# OpenCoffee_V2_DBL_Test.net
KiCad netlist of a schematic drawn in EAGLE
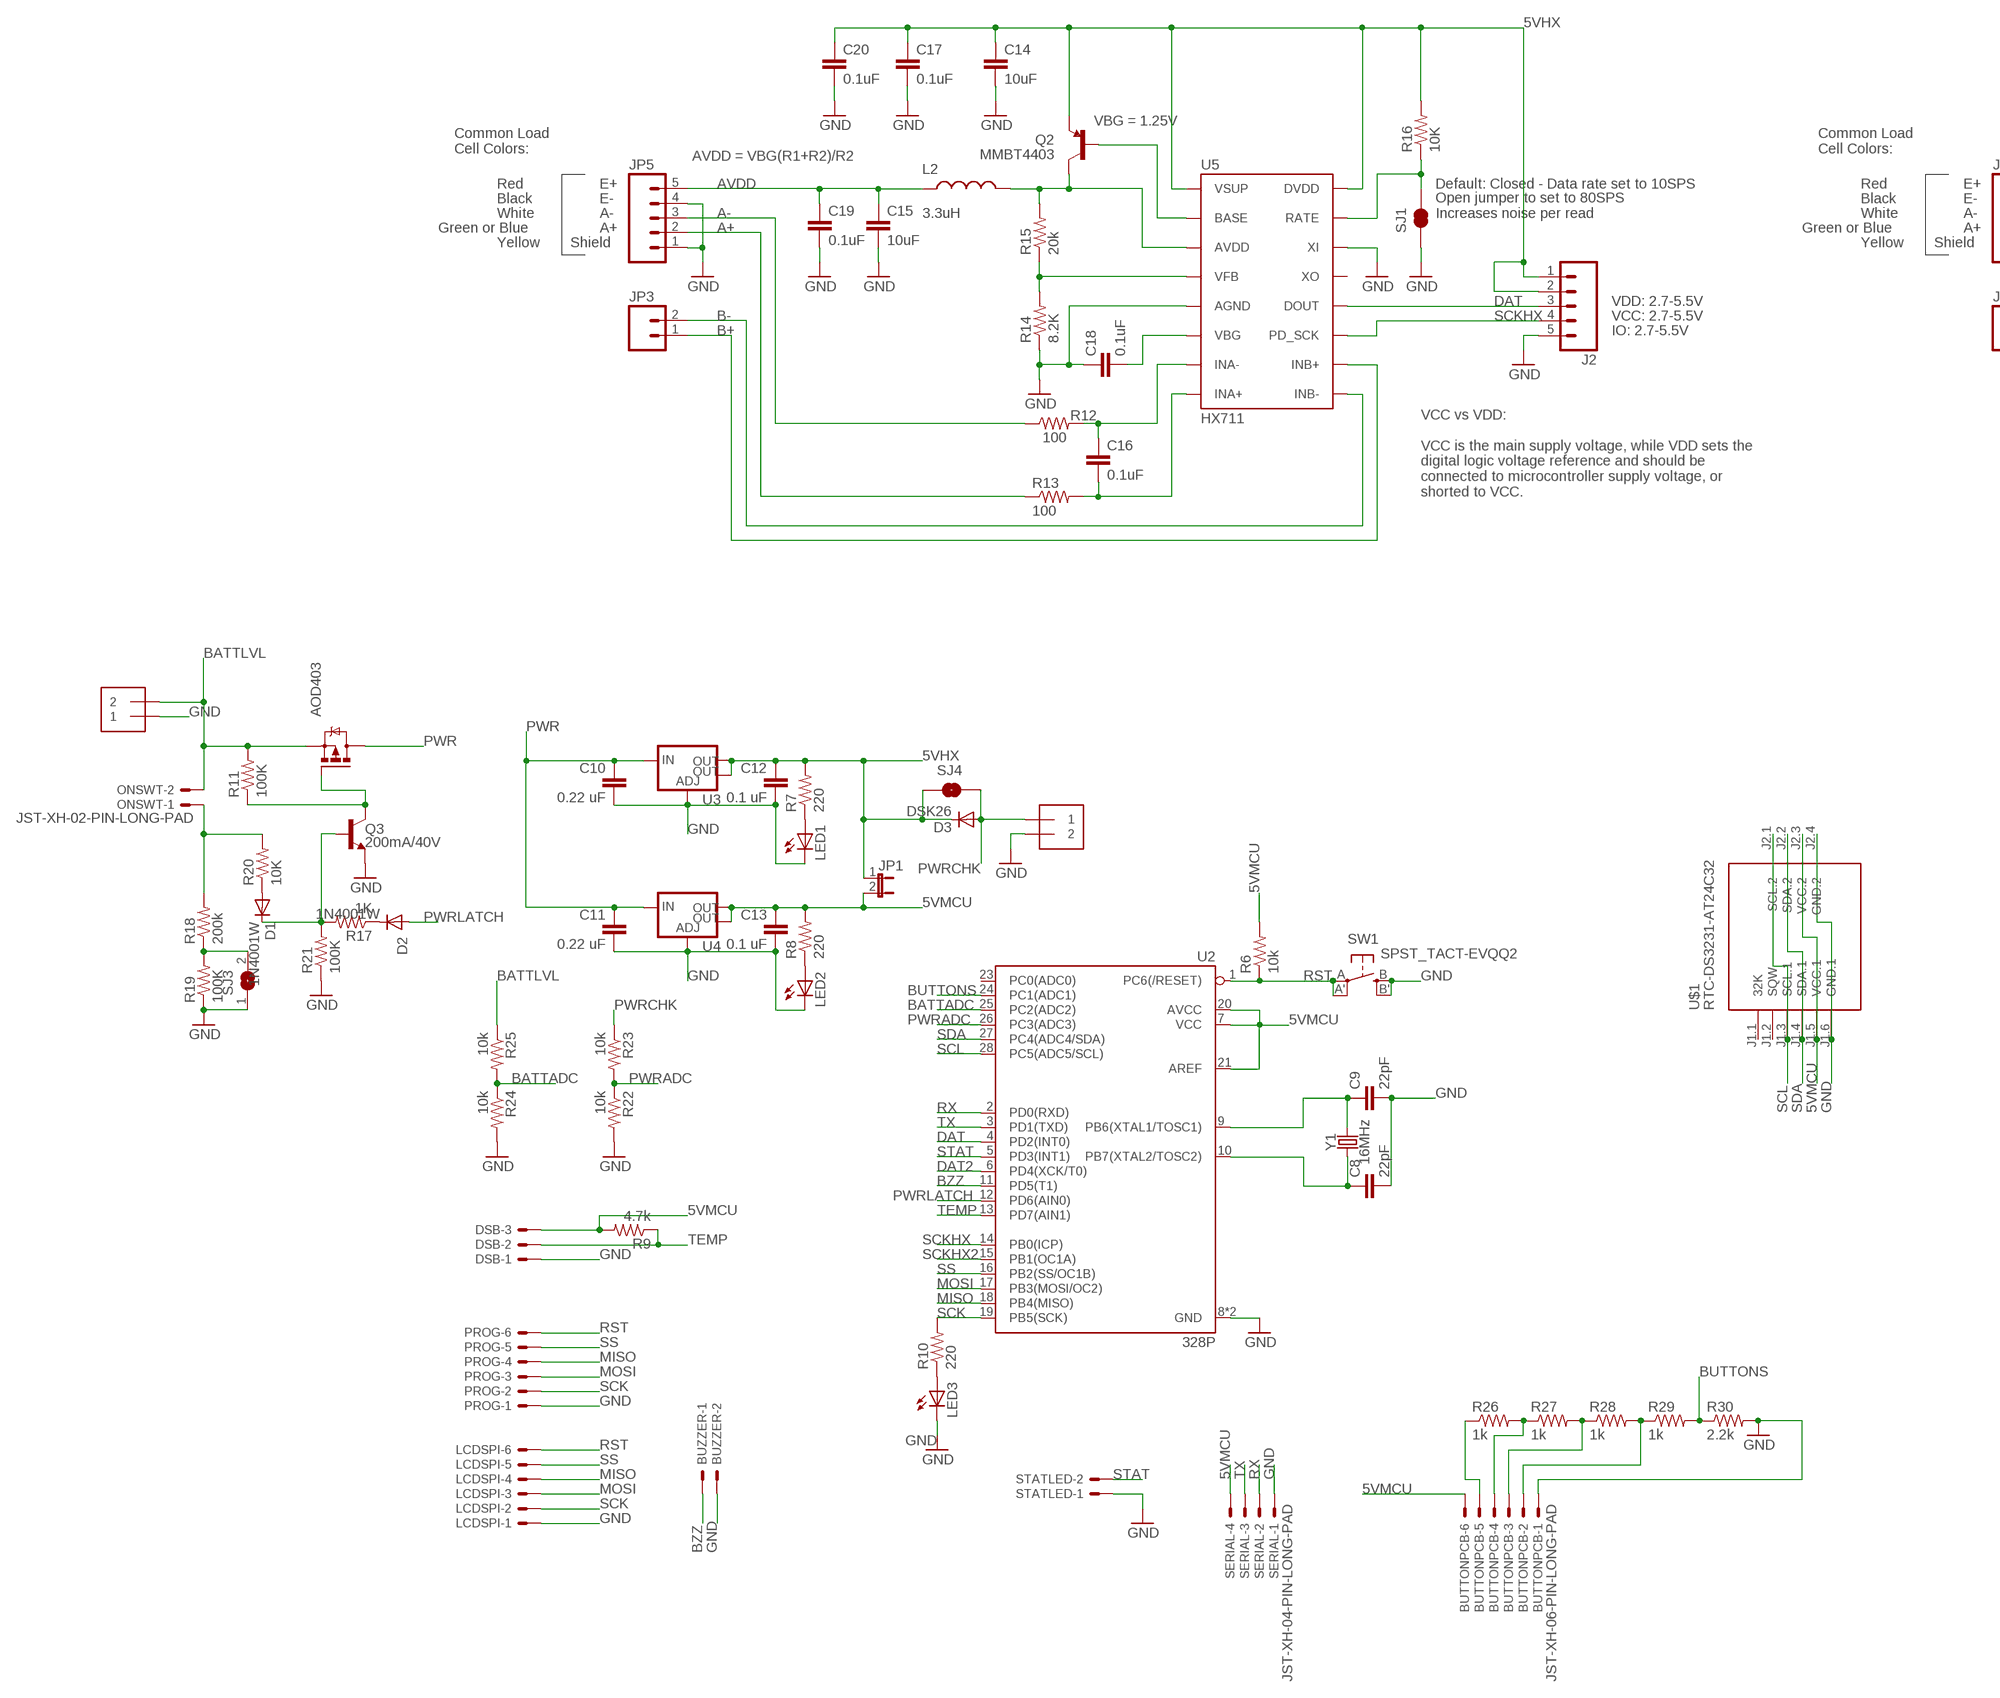
[diagram p0: schematic, sheet 1, part 1 of 2]
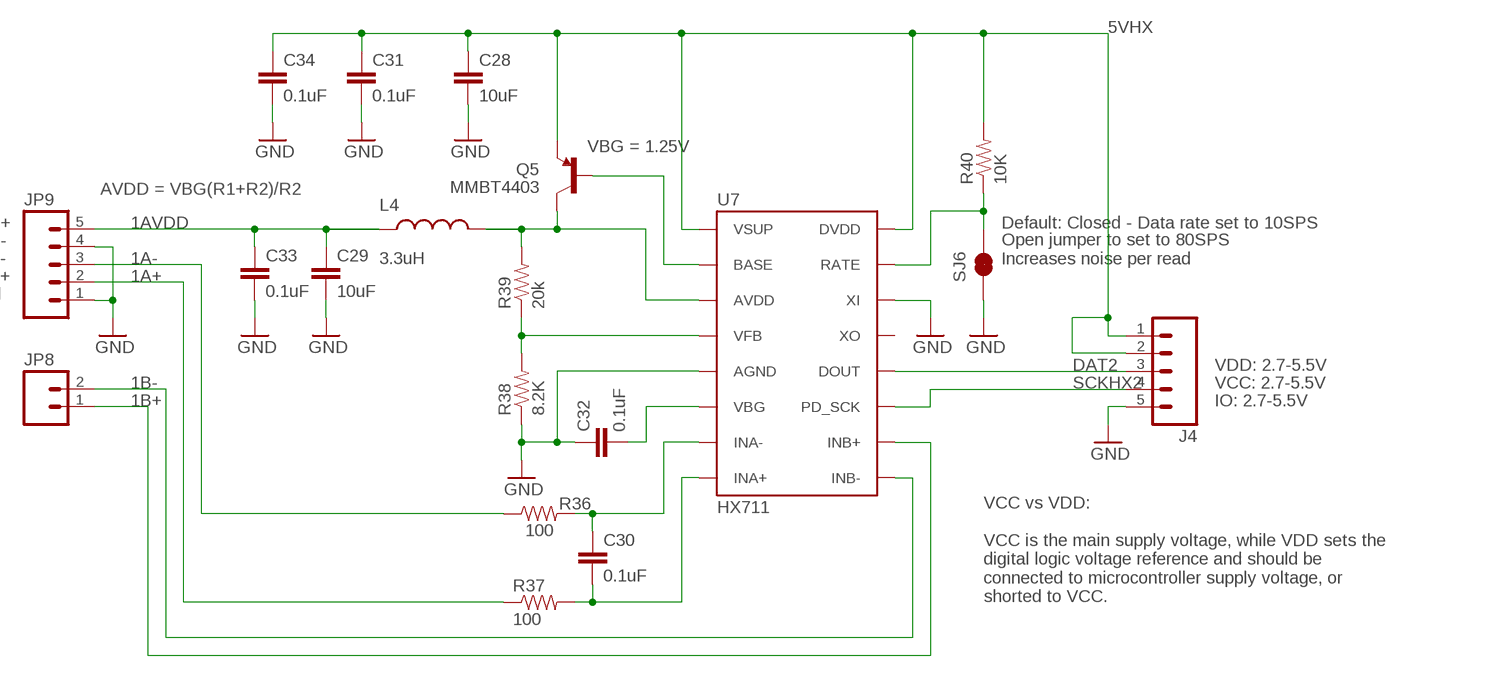
[diagram p1: schematic, sheet 1, part 2 of 2]

(export (version "E")
  (design (tool "Eeschema 10.0.6"))
  (components
    (comp (ref "AOD403")
      (value "IRFR5305")
      (footprint "eagle-import:D-PAK_TO252AA")
      (libsource (lib "eagle-import") (part "IRF?5305R"))
    )
    (comp (ref "BATT")
      (value "1X2-3.5MM")
      (footprint "eagle-import:1X2-3.5MM")
      (libsource (lib "eagle-import") (part "1X2-3.5MM"))
    )
    (comp (ref "BUTTONPCB")
      (value "JST-XH-06-PIN-LONG-PAD")
      (footprint "eagle-import:JST-XH-06-PACKAGE-LONG-PAD")
      (libsource (lib "eagle-import") (part "JST-XH-06-PIN-LONG-PAD"))
    )
    (comp (ref "BUZZER")
      (value "JST-XH-02-PIN-LONG-PAD")
      (footprint "eagle-import:JST-XH-02-PACKAGE-LONG-PAD")
      (libsource (lib "eagle-import") (part "JST-XH-02-PIN-LONG-PAD"))
    )
    (comp (ref "C8")
      (value "22pF")
      (footprint "eagle-import:C1206")
      (libsource (lib "eagle-import") (part "C-EUC1206"))
    )
    (comp (ref "C9")
      (value "22pF")
      (footprint "eagle-import:C1206")
      (libsource (lib "eagle-import") (part "C-EUC1206"))
    )
    (comp (ref "C10")
      (value "0.22 uF")
      (footprint "eagle-import:C1206")
      (libsource (lib "eagle-import") (part "C-EUC1206"))
    )
    (comp (ref "C11")
      (value "0.22 uF")
      (footprint "eagle-import:C1206")
      (libsource (lib "eagle-import") (part "C-EUC1206"))
    )
    (comp (ref "C12")
      (value "0.1 uF")
      (footprint "eagle-import:C1206")
      (libsource (lib "eagle-import") (part "C-EUC1206"))
    )
    (comp (ref "C13")
      (value "0.1 uF")
      (footprint "eagle-import:C1206")
      (libsource (lib "eagle-import") (part "C-EUC1206"))
    )
    (comp (ref "C14")
      (value "10uF")
      (footprint "eagle-import:1210")
      (libsource (lib "eagle-import") (part "10UF50V20%(1210)"))
    )
    (comp (ref "C15")
      (value "10uF")
      (footprint "eagle-import:1210")
      (libsource (lib "eagle-import") (part "10UF50V20%(1210)"))
    )
    (comp (ref "C16")
      (value "0.1uF")
      (footprint "eagle-import:0603-CAP")
      (libsource (lib "eagle-import") (part "0.1UF-25V-5%(0603)"))
    )
    (comp (ref "C17")
      (value "0.1uF")
      (footprint "eagle-import:0603-CAP")
      (libsource (lib "eagle-import") (part "0.1UF-25V-5%(0603)"))
    )
    (comp (ref "C18")
      (value "0.1uF")
      (footprint "eagle-import:0603-CAP")
      (libsource (lib "eagle-import") (part "0.1UF-25V-5%(0603)"))
    )
    (comp (ref "C19")
      (value "0.1uF")
      (footprint "eagle-import:0603-CAP")
      (libsource (lib "eagle-import") (part "0.1UF-25V-5%(0603)"))
    )
    (comp (ref "C20")
      (value "0.1uF")
      (footprint "eagle-import:0603-CAP")
      (libsource (lib "eagle-import") (part "0.1UF-25V-5%(0603)"))
    )
    (comp (ref "C28")
      (value "10uF")
      (footprint "eagle-import:1210")
      (libsource (lib "eagle-import") (part "10UF50V20%(1210)"))
    )
    (comp (ref "C29")
      (value "10uF")
      (footprint "eagle-import:1210")
      (libsource (lib "eagle-import") (part "10UF50V20%(1210)"))
    )
    (comp (ref "C30")
      (value "0.1uF")
      (footprint "eagle-import:0603-CAP")
      (libsource (lib "eagle-import") (part "0.1UF-25V-5%(0603)"))
    )
    (comp (ref "C31")
      (value "0.1uF")
      (footprint "eagle-import:0603-CAP")
      (libsource (lib "eagle-import") (part "0.1UF-25V-5%(0603)"))
    )
    (comp (ref "C32")
      (value "0.1uF")
      (footprint "eagle-import:0603-CAP")
      (libsource (lib "eagle-import") (part "0.1UF-25V-5%(0603)"))
    )
    (comp (ref "C33")
      (value "0.1uF")
      (footprint "eagle-import:0603-CAP")
      (libsource (lib "eagle-import") (part "0.1UF-25V-5%(0603)"))
    )
    (comp (ref "C34")
      (value "0.1uF")
      (footprint "eagle-import:0603-CAP")
      (libsource (lib "eagle-import") (part "0.1UF-25V-5%(0603)"))
    )
    (comp (ref "D1")
      (value "1N4001W")
      (footprint "eagle-import:SOD123")
      (libsource (lib "eagle-import") (part "DIODE-SOD123"))
    )
    (comp (ref "D2")
      (value "1N4001W")
      (footprint "eagle-import:SOD123")
      (libsource (lib "eagle-import") (part "DIODE-SOD123"))
    )
    (comp (ref "D3")
      (value "DSK26")
      (footprint "eagle-import:SOD123")
      (libsource (lib "eagle-import") (part "DIODE-SOD123"))
    )
    (comp (ref "DSB")
      (value "JST-XH-03-PIN-LONG-PAD")
      (footprint "eagle-import:JST-XH-03-PACKAGE-LONG-PAD")
      (libsource (lib "eagle-import") (part "JST-XH-03-PIN-LONG-PAD"))
    )
    (comp (ref "J2")
      (value "M05PTH")
      (footprint "eagle-import:1X05")
      (libsource (lib "eagle-import") (part "M05PTH"))
    )
    (comp (ref "J4")
      (value "M05PTH")
      (footprint "eagle-import:1X05")
      (libsource (lib "eagle-import") (part "M05PTH"))
    )
    (comp (ref "JP1")
      (value "JP1E")
      (footprint "eagle-import:JP1")
      (libsource (lib "eagle-import") (part "JP1E"))
    )
    (comp (ref "JP3")
      (value "M02PTH")
      (footprint "eagle-import:1X02")
      (libsource (lib "eagle-import") (part "M02PTH"))
    )
    (comp (ref "JP5")
      (value "M05PTH")
      (footprint "eagle-import:1X05")
      (libsource (lib "eagle-import") (part "M05PTH"))
    )
    (comp (ref "JP8")
      (value "M02PTH")
      (footprint "eagle-import:1X02")
      (libsource (lib "eagle-import") (part "M02PTH"))
    )
    (comp (ref "JP9")
      (value "M05PTH")
      (footprint "eagle-import:1X05")
      (libsource (lib "eagle-import") (part "M05PTH"))
    )
    (comp (ref "L2")
      (value "3.3uH")
      (footprint "eagle-import:0805")
      (libsource (lib "eagle-import") (part "INDUCTOR0805-IND"))
    )
    (comp (ref "L4")
      (value "3.3uH")
      (footprint "eagle-import:0805")
      (libsource (lib "eagle-import") (part "INDUCTOR0805-IND"))
    )
    (comp (ref "LCDSPI")
      (value "JST-XH-06-PIN-LONG-PAD")
      (footprint "eagle-import:JST-XH-06-PACKAGE-LONG-PAD")
      (libsource (lib "eagle-import") (part "JST-XH-06-PIN-LONG-PAD"))
    )
    (comp (ref "LED1")
      (value "LEDCHIPLED_1206")
      (footprint "eagle-import:CHIPLED_1206")
      (libsource (lib "eagle-import") (part "LEDCHIPLED_1206"))
    )
    (comp (ref "LED2")
      (value "LEDCHIPLED_1206")
      (footprint "eagle-import:CHIPLED_1206")
      (libsource (lib "eagle-import") (part "LEDCHIPLED_1206"))
    )
    (comp (ref "LED3")
      (value "LEDCHIPLED_1206")
      (footprint "eagle-import:CHIPLED_1206")
      (libsource (lib "eagle-import") (part "LEDCHIPLED_1206"))
    )
    (comp (ref "ONSWT")
      (value "JST-XH-02-PIN-LONG-PAD")
      (footprint "eagle-import:JST-XH-02-PACKAGE-LONG-PAD")
      (libsource (lib "eagle-import") (part "JST-XH-02-PIN-LONG-PAD"))
    )
    (comp (ref "PROG")
      (value "JST-XH-06-PIN-LONG-PAD")
      (footprint "eagle-import:JST-XH-06-PACKAGE-LONG-PAD")
      (libsource (lib "eagle-import") (part "JST-XH-06-PIN-LONG-PAD"))
    )
    (comp (ref "Q2")
      (value "MMBT4403")
      (footprint "eagle-import:SOT23-3")
      (libsource (lib "eagle-import") (part "TRANSISTOR_PNPMMBT4403"))
    )
    (comp (ref "Q3")
      (value "200mA/40V")
      (footprint "eagle-import:TO-92@1")
      (libsource (lib "eagle-import") (part "TRANS_NPN-2N3904"))
    )
    (comp (ref "Q5")
      (value "MMBT4403")
      (footprint "eagle-import:SOT23-3")
      (libsource (lib "eagle-import") (part "TRANSISTOR_PNPMMBT4403"))
    )
    (comp (ref "R6")
      (value "10k")
      (footprint "eagle-import:R1206")
      (libsource (lib "eagle-import") (part "R-US_R1206"))
    )
    (comp (ref "R7")
      (value "220")
      (footprint "eagle-import:R1206")
      (libsource (lib "eagle-import") (part "R-US_R1206"))
    )
    (comp (ref "R8")
      (value "220")
      (footprint "eagle-import:R1206")
      (libsource (lib "eagle-import") (part "R-US_R1206"))
    )
    (comp (ref "R9")
      (value "4.7k")
      (footprint "eagle-import:R1206")
      (libsource (lib "eagle-import") (part "R-US_R1206"))
    )
    (comp (ref "R10")
      (value "220")
      (footprint "eagle-import:R1206")
      (libsource (lib "eagle-import") (part "R-US_R1206"))
    )
    (comp (ref "R11")
      (value "100K")
      (footprint "eagle-import:R1206")
      (libsource (lib "eagle-import") (part "R-US_R1206"))
    )
    (comp (ref "R12")
      (value "100")
      (footprint "eagle-import:0603-RES")
      (libsource (lib "eagle-import") (part "100OHM-1/10W-1%(0603)"))
    )
    (comp (ref "R13")
      (value "100")
      (footprint "eagle-import:0603-RES")
      (libsource (lib "eagle-import") (part "100OHM-1/10W-1%(0603)"))
    )
    (comp (ref "R14")
      (value "8.2K")
      (footprint "eagle-import:0603-RES")
      (libsource (lib "eagle-import") (part "8.2KOHM-1/10W-5%(0603)"))
    )
    (comp (ref "R15")
      (value "20k")
      (footprint "eagle-import:0603-RES")
      (libsource (lib "eagle-import") (part "20KOHM1/10W1%(0603)"))
    )
    (comp (ref "R16")
      (value "10K")
      (footprint "eagle-import:0603-RES")
      (libsource (lib "eagle-import") (part "10KOHM-1/10W-1%(0603)0603"))
    )
    (comp (ref "R17")
      (value "1K")
      (footprint "eagle-import:R1206")
      (libsource (lib "eagle-import") (part "R-US_R1206"))
    )
    (comp (ref "R18")
      (value "200k")
      (footprint "eagle-import:R1206")
      (libsource (lib "eagle-import") (part "R-US_R1206"))
    )
    (comp (ref "R19")
      (value "100K")
      (footprint "eagle-import:R1206")
      (libsource (lib "eagle-import") (part "R-US_R1206"))
    )
    (comp (ref "R20")
      (value "10K")
      (footprint "eagle-import:R1206")
      (libsource (lib "eagle-import") (part "R-US_R1206"))
    )
    (comp (ref "R21")
      (value "100K")
      (footprint "eagle-import:R1206")
      (libsource (lib "eagle-import") (part "R-US_R1206"))
    )
    (comp (ref "R22")
      (value "10k")
      (footprint "eagle-import:R1206")
      (libsource (lib "eagle-import") (part "R-US_R1206"))
    )
    (comp (ref "R23")
      (value "10k")
      (footprint "eagle-import:R1206")
      (libsource (lib "eagle-import") (part "R-US_R1206"))
    )
    (comp (ref "R24")
      (value "10k")
      (footprint "eagle-import:R1206")
      (libsource (lib "eagle-import") (part "R-US_R1206"))
    )
    (comp (ref "R25")
      (value "10k")
      (footprint "eagle-import:R1206")
      (libsource (lib "eagle-import") (part "R-US_R1206"))
    )
    (comp (ref "R26")
      (value "1k")
      (footprint "eagle-import:R1206")
      (libsource (lib "eagle-import") (part "R-US_R1206"))
    )
    (comp (ref "R27")
      (value "1k")
      (footprint "eagle-import:R1206")
      (libsource (lib "eagle-import") (part "R-US_R1206"))
    )
    (comp (ref "R28")
      (value "1k")
      (footprint "eagle-import:R1206")
      (libsource (lib "eagle-import") (part "R-US_R1206"))
    )
    (comp (ref "R29")
      (value "1k")
      (footprint "eagle-import:R1206")
      (libsource (lib "eagle-import") (part "R-US_R1206"))
    )
    (comp (ref "R30")
      (value "2.2k")
      (footprint "eagle-import:R1206")
      (libsource (lib "eagle-import") (part "R-US_R1206"))
    )
    (comp (ref "R36")
      (value "100")
      (footprint "eagle-import:0603-RES")
      (libsource (lib "eagle-import") (part "100OHM-1/10W-1%(0603)"))
    )
    (comp (ref "R37")
      (value "100")
      (footprint "eagle-import:0603-RES")
      (libsource (lib "eagle-import") (part "100OHM-1/10W-1%(0603)"))
    )
    (comp (ref "R38")
      (value "8.2K")
      (footprint "eagle-import:0603-RES")
      (libsource (lib "eagle-import") (part "8.2KOHM-1/10W-5%(0603)"))
    )
    (comp (ref "R39")
      (value "20k")
      (footprint "eagle-import:0603-RES")
      (libsource (lib "eagle-import") (part "20KOHM1/10W1%(0603)"))
    )
    (comp (ref "R40")
      (value "10K")
      (footprint "eagle-import:0603-RES")
      (libsource (lib "eagle-import") (part "10KOHM-1/10W-1%(0603)0603"))
    )
    (comp (ref "SERIAL")
      (value "JST-XH-04-PIN-LONG-PAD")
      (footprint "eagle-import:JST-XH-04-PACKAGE-LONG-PAD")
      (libsource (lib "eagle-import") (part "JST-XH-04-PIN-LONG-PAD"))
    )
    (comp (ref "SJ1")
      (value "JUMPER-PAD-2-NC_BY_TRACE")
      (footprint "eagle-import:PAD-JUMPER-2-NC_BY_TRACE_YES_SILK")
      (libsource (lib "eagle-import") (part "JUMPER-PAD-2-NC_BY_TRACE"))
    )
    (comp (ref "SJ3") (value "SJ") (footprint "eagle-import:SJ") (libsource (lib "eagle-import") (part "SJ")))
    (comp (ref "SJ4")
      (value "SOLDERJUMPERNO")
      (footprint "eagle-import:SJ_2S-NO")
      (libsource (lib "eagle-import") (part "SOLDERJUMPERNO"))
    )
    (comp (ref "SJ6")
      (value "JUMPER-PAD-2-NC_BY_TRACE")
      (footprint "eagle-import:PAD-JUMPER-2-NC_BY_TRACE_YES_SILK")
      (libsource (lib "eagle-import") (part "JUMPER-PAD-2-NC_BY_TRACE"))
    )
    (comp (ref "STATLED")
      (value "JST-XH-02-PIN-LONG-PAD")
      (footprint "eagle-import:JST-XH-02-PACKAGE-LONG-PAD")
      (libsource (lib "eagle-import") (part "JST-XH-02-PIN-LONG-PAD"))
    )
    (comp (ref "SW1")
      (value "SPST_TACT-EVQQ2")
      (footprint "eagle-import:EVQ-Q2")
      (libsource (lib "eagle-import") (part "SPST_TACT-EVQQ2"))
    )
    (comp (ref "U$1")
      (value "RTC-DS3231-AT24C32")
      (footprint "eagle-import:RTC-DS3231-AT24C32")
      (libsource (lib "eagle-import") (part "RTC-DS3231-AT24C32"))
    )
    (comp (ref "U2")
      (value "328P")
      (footprint "eagle-import:DIP28")
      (libsource (lib "eagle-import") (part "ATMEGA328P_PDIP"))
    )
    (comp (ref "U3")
      (value "V_REG_LM1117SOT223")
      (footprint "eagle-import:SOT223")
      (libsource (lib "eagle-import") (part "V_REG_LM1117SOT223"))
    )
    (comp (ref "U4")
      (value "V_REG_LM1117SOT223")
      (footprint "eagle-import:SOT223")
      (libsource (lib "eagle-import") (part "V_REG_LM1117SOT223"))
    )
    (comp (ref "U5")
      (value "HX711")
      (footprint "eagle-import:SO16")
      (libsource (lib "eagle-import") (part "HX711HX711"))
    )
    (comp (ref "U7")
      (value "HX711")
      (footprint "eagle-import:SO16")
      (libsource (lib "eagle-import") (part "HX711HX711"))
    )
    (comp (ref "USBPWR")
      (value "1X2-3.5MM")
      (footprint "eagle-import:1X2-3.5MM")
      (libsource (lib "eagle-import") (part "1X2-3.5MM"))
    )
    (comp (ref "Y1")
      (value "16MHz")
      (footprint "eagle-import:HC49US")
      (libsource (lib "eagle-import") (part "CRYSTAL-16MHZPTH-HC49US"))
    )
  )
  (nets
    (net (code "1") (name "/1A+") (class "Default")
      (node (ref "JP9") (pin "2") (pinfunction "2_2") (pintype "passive"))
      (node (ref "R37") (pin "1") (pinfunction "1_1") (pintype "passive"))
    )
    (net (code "2") (name "/1A-") (class "Default")
      (node (ref "JP9") (pin "3") (pinfunction "3_3") (pintype "passive"))
      (node (ref "R36") (pin "1") (pinfunction "1_1") (pintype "passive"))
    )
    (net (code "3") (name "/1AVDD") (class "Default")
      (node (ref "C29") (pin "1") (pinfunction "1_1") (pintype "passive"))
      (node (ref "C33") (pin "1") (pinfunction "1_1") (pintype "passive"))
      (node (ref "JP9") (pin "5") (pinfunction "5_5") (pintype "passive"))
      (node (ref "L4") (pin "1") (pinfunction "1_1") (pintype "passive"))
    )
    (net (code "4") (name "/1B+") (class "Default")
      (node (ref "JP8") (pin "1") (pinfunction "1_1") (pintype "passive"))
      (node (ref "U7") (pin "10") (pinfunction "INB+_10") (pintype "bidirectional"))
    )
    (net (code "5") (name "/1B-") (class "Default")
      (node (ref "JP8") (pin "2") (pinfunction "2_2") (pintype "passive"))
      (node (ref "U7") (pin "9") (pinfunction "INB-_9") (pintype "bidirectional"))
    )
    (net (code "6") (name "/5VHX") (class "Default")
      (node (ref "C12") (pin "1") (pinfunction "1_1") (pintype "passive"))
      (node (ref "C14") (pin "1") (pinfunction "1_1") (pintype "passive"))
      (node (ref "C17") (pin "1") (pinfunction "1_1") (pintype "passive"))
      (node (ref "C20") (pin "1") (pinfunction "1_1") (pintype "passive"))
      (node (ref "C28") (pin "1") (pinfunction "1_1") (pintype "passive"))
      (node (ref "C31") (pin "1") (pinfunction "1_1") (pintype "passive"))
      (node (ref "C34") (pin "1") (pinfunction "1_1") (pintype "passive"))
      (node (ref "D3") (pin "C") (pinfunction "C_C") (pintype "passive"))
      (node (ref "J2") (pin "1") (pinfunction "1_1") (pintype "passive"))
      (node (ref "J2") (pin "2") (pinfunction "2_2") (pintype "passive"))
      (node (ref "J4") (pin "1") (pinfunction "1_1") (pintype "passive"))
      (node (ref "J4") (pin "2") (pinfunction "2_2") (pintype "passive"))
      (node (ref "JP1") (pin "1") (pinfunction "1_1") (pintype "passive"))
      (node (ref "Q2") (pin "2") (pinfunction "E_2") (pintype "passive"))
      (node (ref "Q5") (pin "2") (pinfunction "E_2") (pintype "passive"))
      (node (ref "R16") (pin "2") (pinfunction "2_2") (pintype "passive"))
      (node (ref "R40") (pin "2") (pinfunction "2_2") (pintype "passive"))
      (node (ref "R7") (pin "2") (pinfunction "2_2") (pintype "passive"))
      (node (ref "SJ4") (pin "1") (pinfunction "1_1") (pintype "passive"))
      (node (ref "U3") (pin "2") (pinfunction "OUT_2") (pintype "output"))
      (node (ref "U3") (pin "4") (pinfunction "OUT_4") (pintype "output"))
      (node (ref "U5") (pin "1") (pinfunction "VSUP_1") (pintype "bidirectional"))
      (node (ref "U5") (pin "16") (pinfunction "DVDD_16") (pintype "bidirectional"))
      (node (ref "U7") (pin "1") (pinfunction "VSUP_1") (pintype "bidirectional"))
      (node (ref "U7") (pin "16") (pinfunction "DVDD_16") (pintype "bidirectional"))
    )
    (net (code "7") (name "/5VMCU") (class "Default")
      (node (ref "BUTTONPCB") (pin "6") (pinfunction "S_6") (pintype "passive"))
      (node (ref "C13") (pin "1") (pinfunction "1_1") (pintype "passive"))
      (node (ref "DSB") (pin "3") (pinfunction "S_3") (pintype "passive"))
      (node (ref "JP1") (pin "2") (pinfunction "2_2") (pintype "passive"))
      (node (ref "R6") (pin "2") (pinfunction "2_2") (pintype "passive"))
      (node (ref "R8") (pin "2") (pinfunction "2_2") (pintype "passive"))
      (node (ref "R9") (pin "2") (pinfunction "2_2") (pintype "passive"))
      (node (ref "SERIAL") (pin "4") (pinfunction "S_4") (pintype "passive"))
      (node (ref "U$1") (pin "J1.5") (pinfunction "VCC.1_J1.5") (pintype "power_in"))
      (node (ref "U$1") (pin "J2.3") (pinfunction "VCC.2_J2.3") (pintype "power_in"))
      (node (ref "U2") (pin "20") (pinfunction "AVCC_20") (pintype "bidirectional"))
      (node (ref "U2") (pin "21") (pinfunction "AREF_21") (pintype "bidirectional"))
      (node (ref "U2") (pin "7") (pinfunction "VCC_7") (pintype "bidirectional"))
      (node (ref "U4") (pin "2") (pinfunction "OUT_2") (pintype "output"))
      (node (ref "U4") (pin "4") (pinfunction "OUT_4") (pintype "output"))
    )
    (net (code "8") (name "/A+") (class "Default")
      (node (ref "JP5") (pin "2") (pinfunction "2_2") (pintype "passive"))
      (node (ref "R13") (pin "1") (pinfunction "1_1") (pintype "passive"))
    )
    (net (code "9") (name "/A-") (class "Default")
      (node (ref "JP5") (pin "3") (pinfunction "3_3") (pintype "passive"))
      (node (ref "R12") (pin "1") (pinfunction "1_1") (pintype "passive"))
    )
    (net (code "10") (name "/AVDD") (class "Default")
      (node (ref "C15") (pin "1") (pinfunction "1_1") (pintype "passive"))
      (node (ref "C19") (pin "1") (pinfunction "1_1") (pintype "passive"))
      (node (ref "JP5") (pin "5") (pinfunction "5_5") (pintype "passive"))
      (node (ref "L2") (pin "1") (pinfunction "1_1") (pintype "passive"))
    )
    (net (code "11") (name "/B+") (class "Default")
      (node (ref "JP3") (pin "1") (pinfunction "1_1") (pintype "passive"))
      (node (ref "U5") (pin "10") (pinfunction "INB+_10") (pintype "bidirectional"))
    )
    (net (code "12") (name "/B-") (class "Default")
      (node (ref "JP3") (pin "2") (pinfunction "2_2") (pintype "passive"))
      (node (ref "U5") (pin "9") (pinfunction "INB-_9") (pintype "bidirectional"))
    )
    (net (code "13") (name "/BATTADC") (class "Default")
      (node (ref "R24") (pin "1") (pinfunction "1_1") (pintype "passive"))
      (node (ref "R25") (pin "2") (pinfunction "2_2") (pintype "passive"))
      (node (ref "U2") (pin "25") (pinfunction "PC2(ADC2)_25") (pintype "bidirectional"))
    )
    (net (code "14") (name "/BATTLVL") (class "Default")
      (node (ref "AOD403") (pin "3") (pinfunction "S_3") (pintype "passive"))
      (node (ref "BATT") (pin "2") (pinfunction "2_2") (pintype "passive"))
      (node (ref "ONSWT") (pin "2") (pinfunction "S_2") (pintype "passive"))
      (node (ref "R11") (pin "2") (pinfunction "2_2") (pintype "passive"))
      (node (ref "R25") (pin "1") (pinfunction "1_1") (pintype "passive"))
    )
    (net (code "15") (name "/BUTTONS") (class "Default")
      (node (ref "R29") (pin "2") (pinfunction "2_2") (pintype "passive"))
      (node (ref "R30") (pin "1") (pinfunction "1_1") (pintype "passive"))
      (node (ref "U2") (pin "24") (pinfunction "PC1(ADC1)_24") (pintype "bidirectional"))
    )
    (net (code "16") (name "/BZZ") (class "Default")
      (node (ref "BUZZER") (pin "1") (pinfunction "S_1") (pintype "passive"))
      (node (ref "U2") (pin "11") (pinfunction "PD5(T1)_11") (pintype "bidirectional"))
    )
    (net (code "17") (name "/DAT") (class "Default")
      (node (ref "J2") (pin "3") (pinfunction "3_3") (pintype "passive"))
      (node (ref "U2") (pin "4") (pinfunction "PD2(INT0)_4") (pintype "bidirectional"))
      (node (ref "U5") (pin "12") (pinfunction "DOUT_12") (pintype "bidirectional"))
    )
    (net (code "18") (name "/DAT2") (class "Default")
      (node (ref "J4") (pin "3") (pinfunction "3_3") (pintype "passive"))
      (node (ref "U2") (pin "6") (pinfunction "PD4(XCK/T0)_6") (pintype "bidirectional"))
      (node (ref "U7") (pin "12") (pinfunction "DOUT_12") (pintype "bidirectional"))
    )
    (net (code "19") (name "/MISO") (class "Default")
      (node (ref "LCDSPI") (pin "4") (pinfunction "S_4") (pintype "passive"))
      (node (ref "PROG") (pin "4") (pinfunction "S_4") (pintype "passive"))
      (node (ref "U2") (pin "18") (pinfunction "PB4(MISO)_18") (pintype "bidirectional"))
    )
    (net (code "20") (name "/MOSI") (class "Default")
      (node (ref "LCDSPI") (pin "3") (pinfunction "S_3") (pintype "passive"))
      (node (ref "PROG") (pin "3") (pinfunction "S_3") (pintype "passive"))
      (node (ref "U2") (pin "17") (pinfunction "PB3(MOSI/OC2)_17") (pintype "bidirectional"))
    )
    (net (code "21") (name "/PWR") (class "Default")
      (node (ref "AOD403") (pin "4") (pinfunction "D_4") (pintype "passive"))
      (node (ref "C10") (pin "1") (pinfunction "1_1") (pintype "passive"))
      (node (ref "C11") (pin "1") (pinfunction "1_1") (pintype "passive"))
      (node (ref "U3") (pin "3") (pinfunction "IN_3") (pintype "input"))
      (node (ref "U4") (pin "3") (pinfunction "IN_3") (pintype "input"))
    )
    (net (code "22") (name "/PWRADC") (class "Default")
      (node (ref "R22") (pin "1") (pinfunction "1_1") (pintype "passive"))
      (node (ref "R23") (pin "2") (pinfunction "2_2") (pintype "passive"))
      (node (ref "U2") (pin "26") (pinfunction "PC3(ADC3)_26") (pintype "bidirectional"))
    )
    (net (code "23") (name "/PWRCHK") (class "Default")
      (node (ref "D3") (pin "A") (pinfunction "A_A") (pintype "passive"))
      (node (ref "R23") (pin "1") (pinfunction "1_1") (pintype "passive"))
      (node (ref "SJ4") (pin "2") (pinfunction "2_2") (pintype "passive"))
      (node (ref "USBPWR") (pin "1") (pinfunction "1_1") (pintype "passive"))
    )
    (net (code "24") (name "/PWRLATCH") (class "Default")
      (node (ref "D2") (pin "A") (pinfunction "A_A") (pintype "passive"))
      (node (ref "U2") (pin "12") (pinfunction "PD6(AIN0)_12") (pintype "bidirectional"))
    )
    (net (code "25") (name "/RST") (class "Default")
      (node (ref "LCDSPI") (pin "6") (pinfunction "S_6") (pintype "passive"))
      (node (ref "PROG") (pin "6") (pinfunction "S_6") (pintype "passive"))
      (node (ref "R6") (pin "1") (pinfunction "1_1") (pintype "passive"))
      (node (ref "SW1") (pin "A") (pinfunction "P_A") (pintype "passive"))
      (node (ref "SW1") (pin "A'") (pinfunction "P1_A'") (pintype "passive"))
      (node (ref "U2") (pin "1") (pinfunction "PC6(/RESET)_1") (pintype "bidirectional"))
    )
    (net (code "26") (name "/RX") (class "Default")
      (node (ref "SERIAL") (pin "2") (pinfunction "S_2") (pintype "passive"))
      (node (ref "U2") (pin "2") (pinfunction "PD0(RXD)_2") (pintype "bidirectional"))
    )
    (net (code "27") (name "/SCK") (class "Default")
      (node (ref "LCDSPI") (pin "2") (pinfunction "S_2") (pintype "passive"))
      (node (ref "PROG") (pin "2") (pinfunction "S_2") (pintype "passive"))
      (node (ref "R10") (pin "2") (pinfunction "2_2") (pintype "passive"))
      (node (ref "U2") (pin "19") (pinfunction "PB5(SCK)_19") (pintype "bidirectional"))
    )
    (net (code "28") (name "/SCKHX") (class "Default")
      (node (ref "J2") (pin "4") (pinfunction "4_4") (pintype "passive"))
      (node (ref "U2") (pin "14") (pinfunction "PB0(ICP)_14") (pintype "bidirectional"))
      (node (ref "U5") (pin "11") (pinfunction "PD_SCK_11") (pintype "bidirectional"))
    )
    (net (code "29") (name "/SCKHX2") (class "Default")
      (node (ref "J4") (pin "4") (pinfunction "4_4") (pintype "passive"))
      (node (ref "U2") (pin "15") (pinfunction "PB1(OC1A)_15") (pintype "bidirectional"))
      (node (ref "U7") (pin "11") (pinfunction "PD_SCK_11") (pintype "bidirectional"))
    )
    (net (code "30") (name "/SCL") (class "Default")
      (node (ref "U$1") (pin "J1.3") (pinfunction "SCL.1_J1.3") (pintype "bidirectional"))
      (node (ref "U$1") (pin "J2.1") (pinfunction "SCL.2_J2.1") (pintype "bidirectional"))
      (node (ref "U2") (pin "28") (pinfunction "PC5(ADC5/SCL)_28") (pintype "bidirectional"))
    )
    (net (code "31") (name "/SDA") (class "Default")
      (node (ref "U$1") (pin "J1.4") (pinfunction "SDA.1_J1.4") (pintype "bidirectional"))
      (node (ref "U$1") (pin "J2.2") (pinfunction "SDA.2_J2.2") (pintype "bidirectional"))
      (node (ref "U2") (pin "27") (pinfunction "PC4(ADC4/SDA)_27") (pintype "bidirectional"))
    )
    (net (code "32") (name "/SS") (class "Default")
      (node (ref "LCDSPI") (pin "5") (pinfunction "S_5") (pintype "passive"))
      (node (ref "PROG") (pin "5") (pinfunction "S_5") (pintype "passive"))
      (node (ref "U2") (pin "16") (pinfunction "PB2(SS/OC1B)_16") (pintype "bidirectional"))
    )
    (net (code "33") (name "/STAT") (class "Default")
      (node (ref "STATLED") (pin "2") (pinfunction "S_2") (pintype "passive"))
      (node (ref "U2") (pin "5") (pinfunction "PD3(INT1)_5") (pintype "bidirectional"))
    )
    (net (code "34") (name "/TEMP") (class "Default")
      (node (ref "DSB") (pin "2") (pinfunction "S_2") (pintype "passive"))
      (node (ref "R9") (pin "1") (pinfunction "1_1") (pintype "passive"))
      (node (ref "U2") (pin "13") (pinfunction "PD7(AIN1)_13") (pintype "bidirectional"))
    )
    (net (code "35") (name "/TX") (class "Default")
      (node (ref "SERIAL") (pin "3") (pinfunction "S_3") (pintype "passive"))
      (node (ref "U2") (pin "3") (pinfunction "PD1(TXD)_3") (pintype "bidirectional"))
    )
    (net (code "36") (name "GND") (class "Default")
      (node (ref "BATT") (pin "1") (pinfunction "1_1") (pintype "passive"))
      (node (ref "BUTTONPCB") (pin "1") (pinfunction "S_1") (pintype "passive"))
      (node (ref "BUZZER") (pin "2") (pinfunction "S_2") (pintype "passive"))
      (node (ref "C10") (pin "2") (pinfunction "2_2") (pintype "passive"))
      (node (ref "C11") (pin "2") (pinfunction "2_2") (pintype "passive"))
      (node (ref "C12") (pin "2") (pinfunction "2_2") (pintype "passive"))
      (node (ref "C13") (pin "2") (pinfunction "2_2") (pintype "passive"))
      (node (ref "C14") (pin "2") (pinfunction "2_2") (pintype "passive"))
      (node (ref "C15") (pin "2") (pinfunction "2_2") (pintype "passive"))
      (node (ref "C17") (pin "2") (pinfunction "2_2") (pintype "passive"))
      (node (ref "C18") (pin "1") (pinfunction "1_1") (pintype "passive"))
      (node (ref "C19") (pin "2") (pinfunction "2_2") (pintype "passive"))
      (node (ref "C20") (pin "2") (pinfunction "2_2") (pintype "passive"))
      (node (ref "C28") (pin "2") (pinfunction "2_2") (pintype "passive"))
      (node (ref "C29") (pin "2") (pinfunction "2_2") (pintype "passive"))
      (node (ref "C31") (pin "2") (pinfunction "2_2") (pintype "passive"))
      (node (ref "C32") (pin "1") (pinfunction "1_1") (pintype "passive"))
      (node (ref "C33") (pin "2") (pinfunction "2_2") (pintype "passive"))
      (node (ref "C34") (pin "2") (pinfunction "2_2") (pintype "passive"))
      (node (ref "C8") (pin "2") (pinfunction "2_2") (pintype "passive"))
      (node (ref "C9") (pin "2") (pinfunction "2_2") (pintype "passive"))
      (node (ref "DSB") (pin "1") (pinfunction "S_1") (pintype "passive"))
      (node (ref "J2") (pin "5") (pinfunction "5_5") (pintype "passive"))
      (node (ref "J4") (pin "5") (pinfunction "5_5") (pintype "passive"))
      (node (ref "JP5") (pin "1") (pinfunction "1_1") (pintype "passive"))
      (node (ref "JP5") (pin "4") (pinfunction "4_4") (pintype "passive"))
      (node (ref "JP9") (pin "1") (pinfunction "1_1") (pintype "passive"))
      (node (ref "JP9") (pin "4") (pinfunction "4_4") (pintype "passive"))
      (node (ref "LCDSPI") (pin "1") (pinfunction "S_1") (pintype "passive"))
      (node (ref "LED1") (pin "C") (pinfunction "C_C") (pintype "passive"))
      (node (ref "LED2") (pin "C") (pinfunction "C_C") (pintype "passive"))
      (node (ref "LED3") (pin "C") (pinfunction "C_C") (pintype "passive"))
      (node (ref "PROG") (pin "1") (pinfunction "S_1") (pintype "passive"))
      (node (ref "Q3") (pin "1") (pinfunction "E_1") (pintype "passive"))
      (node (ref "R14") (pin "1") (pinfunction "1_1") (pintype "passive"))
      (node (ref "R19") (pin "1") (pinfunction "1_1") (pintype "passive"))
      (node (ref "R21") (pin "1") (pinfunction "1_1") (pintype "passive"))
      (node (ref "R22") (pin "2") (pinfunction "2_2") (pintype "passive"))
      (node (ref "R24") (pin "2") (pinfunction "2_2") (pintype "passive"))
      (node (ref "R30") (pin "2") (pinfunction "2_2") (pintype "passive"))
      (node (ref "R38") (pin "1") (pinfunction "1_1") (pintype "passive"))
      (node (ref "SERIAL") (pin "1") (pinfunction "S_1") (pintype "passive"))
      (node (ref "SJ1") (pin "1") (pinfunction "1_1") (pintype "passive"))
      (node (ref "SJ3") (pin "1") (pinfunction "1_1") (pintype "passive"))
      (node (ref "SJ6") (pin "1") (pinfunction "1_1") (pintype "passive"))
      (node (ref "STATLED") (pin "1") (pinfunction "S_1") (pintype "passive"))
      (node (ref "SW1") (pin "B") (pinfunction "S_B") (pintype "passive"))
      (node (ref "SW1") (pin "B'") (pinfunction "S1_B'") (pintype "passive"))
      (node (ref "U$1") (pin "J1.6") (pinfunction "GND.1_J1.6") (pintype "power_in"))
      (node (ref "U$1") (pin "J2.4") (pinfunction "GND.2_J2.4") (pintype "power_in"))
      (node (ref "U2") (pin "22") (pinfunction "GND_22") (pintype "bidirectional"))
      (node (ref "U2") (pin "8") (pinfunction "GND_8") (pintype "bidirectional"))
      (node (ref "U3") (pin "1") (pinfunction "ADJ_1") (pintype "input"))
      (node (ref "U4") (pin "1") (pinfunction "ADJ_1") (pintype "input"))
      (node (ref "U5") (pin "14") (pinfunction "XI_14") (pintype "bidirectional"))
      (node (ref "U5") (pin "5") (pinfunction "AGND_5") (pintype "bidirectional"))
      (node (ref "U7") (pin "14") (pinfunction "XI_14") (pintype "bidirectional"))
      (node (ref "U7") (pin "5") (pinfunction "AGND_5") (pintype "bidirectional"))
      (node (ref "USBPWR") (pin "2") (pinfunction "2_2") (pintype "passive"))
    )
    (net (code "37") (name "Net-(AOD403-G)") (class "Default")
      (node (ref "AOD403") (pin "1") (pinfunction "G_1") (pintype "passive"))
      (node (ref "Q3") (pin "3") (pinfunction "C_3") (pintype "passive"))
      (node (ref "R11") (pin "1") (pinfunction "1_1") (pintype "passive"))
    )
    (net (code "38") (name "Net-(BUTTONPCBB-S)") (class "Default")
      (node (ref "BUTTONPCB") (pin "2") (pinfunction "S_2") (pintype "passive"))
      (node (ref "R28") (pin "2") (pinfunction "2_2") (pintype "passive"))
      (node (ref "R29") (pin "1") (pinfunction "1_1") (pintype "passive"))
    )
    (net (code "39") (name "Net-(BUTTONPCBC-S)") (class "Default")
      (node (ref "BUTTONPCB") (pin "3") (pinfunction "S_3") (pintype "passive"))
      (node (ref "R27") (pin "2") (pinfunction "2_2") (pintype "passive"))
      (node (ref "R28") (pin "1") (pinfunction "1_1") (pintype "passive"))
    )
    (net (code "40") (name "Net-(BUTTONPCBD-S)") (class "Default")
      (node (ref "BUTTONPCB") (pin "4") (pinfunction "S_4") (pintype "passive"))
      (node (ref "R26") (pin "2") (pinfunction "2_2") (pintype "passive"))
      (node (ref "R27") (pin "1") (pinfunction "1_1") (pintype "passive"))
    )
    (net (code "41") (name "Net-(BUTTONPCBE-S)") (class "Default")
      (node (ref "BUTTONPCB") (pin "5") (pinfunction "S_5") (pintype "passive"))
      (node (ref "R26") (pin "1") (pinfunction "1_1") (pintype "passive"))
    )
    (net (code "42") (name "Net-(D1-PadA)") (class "Default")
      (node (ref "D1") (pin "A") (pinfunction "A_A") (pintype "passive"))
      (node (ref "R20") (pin "1") (pinfunction "1_1") (pintype "passive"))
    )
    (net (code "43") (name "Net-(D2-PadC)") (class "Default")
      (node (ref "D2") (pin "C") (pinfunction "C_C") (pintype "passive"))
      (node (ref "R17") (pin "1") (pinfunction "1_1") (pintype "passive"))
    )
    (net (code "44") (name "Net-(LED1-PadA)") (class "Default")
      (node (ref "LED1") (pin "A") (pinfunction "A_A") (pintype "passive"))
      (node (ref "R7") (pin "1") (pinfunction "1_1") (pintype "passive"))
    )
    (net (code "45") (name "Net-(LED2-PadA)") (class "Default")
      (node (ref "LED2") (pin "A") (pinfunction "A_A") (pintype "passive"))
      (node (ref "R8") (pin "1") (pinfunction "1_1") (pintype "passive"))
    )
    (net (code "46") (name "Net-(LED3-PadA)") (class "Default")
      (node (ref "LED3") (pin "A") (pinfunction "A_A") (pintype "passive"))
      (node (ref "R10") (pin "1") (pinfunction "1_1") (pintype "passive"))
    )
    (net (code "47") (name "Net-(ONSWTA-S)") (class "Default")
      (node (ref "ONSWT") (pin "1") (pinfunction "S_1") (pintype "passive"))
      (node (ref "R18") (pin "2") (pinfunction "2_2") (pintype "passive"))
      (node (ref "R20") (pin "2") (pinfunction "2_2") (pintype "passive"))
    )
    (net (code "48") (name "Net-(Q2-B)") (class "Default")
      (node (ref "Q2") (pin "1") (pinfunction "B_1") (pintype "passive"))
      (node (ref "U5") (pin "2") (pinfunction "BASE_2") (pintype "bidirectional"))
    )
    (net (code "49") (name "Net-(Q2-C)") (class "Default")
      (node (ref "L2") (pin "2") (pinfunction "2_2") (pintype "passive"))
      (node (ref "Q2") (pin "3") (pinfunction "C_3") (pintype "passive"))
      (node (ref "R15") (pin "2") (pinfunction "2_2") (pintype "passive"))
      (node (ref "U5") (pin "3") (pinfunction "AVDD_3") (pintype "bidirectional"))
    )
    (net (code "50") (name "Net-(Q3-B)") (class "Default")
      (node (ref "D1") (pin "C") (pinfunction "C_C") (pintype "passive"))
      (node (ref "Q3") (pin "2") (pinfunction "B_2") (pintype "passive"))
      (node (ref "R17") (pin "2") (pinfunction "2_2") (pintype "passive"))
      (node (ref "R21") (pin "2") (pinfunction "2_2") (pintype "passive"))
    )
    (net (code "51") (name "Net-(Q5-B)") (class "Default")
      (node (ref "Q5") (pin "1") (pinfunction "B_1") (pintype "passive"))
      (node (ref "U7") (pin "2") (pinfunction "BASE_2") (pintype "bidirectional"))
    )
    (net (code "52") (name "Net-(Q5-C)") (class "Default")
      (node (ref "L4") (pin "2") (pinfunction "2_2") (pintype "passive"))
      (node (ref "Q5") (pin "3") (pinfunction "C_3") (pintype "passive"))
      (node (ref "R39") (pin "2") (pinfunction "2_2") (pintype "passive"))
      (node (ref "U7") (pin "3") (pinfunction "AVDD_3") (pintype "bidirectional"))
    )
    (net (code "53") (name "Net-(R18-Pad1)") (class "Default")
      (node (ref "R18") (pin "1") (pinfunction "1_1") (pintype "passive"))
      (node (ref "R19") (pin "2") (pinfunction "2_2") (pintype "passive"))
      (node (ref "SJ3") (pin "2") (pinfunction "2_2") (pintype "passive"))
    )
    (net (code "54") (name "Net-(U2-PB6(XTAL1{slash}TOSC1))") (class "Default")
      (node (ref "C9") (pin "1") (pinfunction "1_1") (pintype "passive"))
      (node (ref "U2") (pin "9") (pinfunction "PB6(XTAL1/TOSC1)_9") (pintype "bidirectional"))
      (node (ref "Y1") (pin "2") (pinfunction "2_2") (pintype "passive"))
    )
    (net (code "55") (name "Net-(U2-PB7(XTAL2{slash}TOSC2))") (class "Default")
      (node (ref "C8") (pin "1") (pinfunction "1_1") (pintype "passive"))
      (node (ref "U2") (pin "10") (pinfunction "PB7(XTAL2/TOSC2)_10") (pintype "bidirectional"))
      (node (ref "Y1") (pin "1") (pinfunction "1_1") (pintype "passive"))
    )
    (net (code "56") (name "Net-(U5-INA+)") (class "Default")
      (node (ref "C16") (pin "2") (pinfunction "2_2") (pintype "passive"))
      (node (ref "R13") (pin "2") (pinfunction "2_2") (pintype "passive"))
      (node (ref "U5") (pin "8") (pinfunction "INA+_8") (pintype "bidirectional"))
    )
    (net (code "57") (name "Net-(U5-INA-)") (class "Default")
      (node (ref "C16") (pin "1") (pinfunction "1_1") (pintype "passive"))
      (node (ref "R12") (pin "2") (pinfunction "2_2") (pintype "passive"))
      (node (ref "U5") (pin "7") (pinfunction "INA-_7") (pintype "bidirectional"))
    )
    (net (code "58") (name "Net-(U5-RATE)") (class "Default")
      (node (ref "R16") (pin "1") (pinfunction "1_1") (pintype "passive"))
      (node (ref "SJ1") (pin "2") (pinfunction "2_2") (pintype "passive"))
      (node (ref "U5") (pin "15") (pinfunction "RATE_15") (pintype "bidirectional"))
    )
    (net (code "59") (name "Net-(U5-VBG)") (class "Default")
      (node (ref "C18") (pin "2") (pinfunction "2_2") (pintype "passive"))
      (node (ref "U5") (pin "6") (pinfunction "VBG_6") (pintype "bidirectional"))
    )
    (net (code "60") (name "Net-(U5-VFB)") (class "Default")
      (node (ref "R14") (pin "2") (pinfunction "2_2") (pintype "passive"))
      (node (ref "R15") (pin "1") (pinfunction "1_1") (pintype "passive"))
      (node (ref "U5") (pin "4") (pinfunction "VFB_4") (pintype "bidirectional"))
    )
    (net (code "61") (name "Net-(U7-INA+)") (class "Default")
      (node (ref "C30") (pin "2") (pinfunction "2_2") (pintype "passive"))
      (node (ref "R37") (pin "2") (pinfunction "2_2") (pintype "passive"))
      (node (ref "U7") (pin "8") (pinfunction "INA+_8") (pintype "bidirectional"))
    )
    (net (code "62") (name "Net-(U7-INA-)") (class "Default")
      (node (ref "C30") (pin "1") (pinfunction "1_1") (pintype "passive"))
      (node (ref "R36") (pin "2") (pinfunction "2_2") (pintype "passive"))
      (node (ref "U7") (pin "7") (pinfunction "INA-_7") (pintype "bidirectional"))
    )
    (net (code "63") (name "Net-(U7-RATE)") (class "Default")
      (node (ref "R40") (pin "1") (pinfunction "1_1") (pintype "passive"))
      (node (ref "SJ6") (pin "2") (pinfunction "2_2") (pintype "passive"))
      (node (ref "U7") (pin "15") (pinfunction "RATE_15") (pintype "bidirectional"))
    )
    (net (code "64") (name "Net-(U7-VBG)") (class "Default")
      (node (ref "C32") (pin "2") (pinfunction "2_2") (pintype "passive"))
      (node (ref "U7") (pin "6") (pinfunction "VBG_6") (pintype "bidirectional"))
    )
    (net (code "65") (name "Net-(U7-VFB)") (class "Default")
      (node (ref "R38") (pin "2") (pinfunction "2_2") (pintype "passive"))
      (node (ref "R39") (pin "1") (pinfunction "1_1") (pintype "passive"))
      (node (ref "U7") (pin "4") (pinfunction "VFB_4") (pintype "bidirectional"))
    )
    (net (code "66") (name "unconnected-(U$1-32K-PadJ1.1)") (class "Default")
      (node (ref "U$1") (pin "J1.1") (pinfunction "32K_J1.1") (pintype "bidirectional"))
    )
    (net (code "67") (name "unconnected-(U$1-SQW-PadJ1.2)") (class "Default")
      (node (ref "U$1") (pin "J1.2") (pinfunction "SQW_J1.2") (pintype "bidirectional"))
    )
    (net (code "68") (name "unconnected-(U2-PC0(ADC0)-Pad23)") (class "Default")
      (node (ref "U2") (pin "23") (pinfunction "PC0(ADC0)_23") (pintype "bidirectional"))
    )
    (net (code "69") (name "unconnected-(U5-XO-Pad13)") (class "Default")
      (node (ref "U5") (pin "13") (pinfunction "XO_13") (pintype "bidirectional"))
    )
    (net (code "70") (name "unconnected-(U7-XO-Pad13)") (class "Default")
      (node (ref "U7") (pin "13") (pinfunction "XO_13") (pintype "bidirectional"))
    )
  )
)
